# LV1.net
KiCad netlist of a schematic drawn in Altium Designer
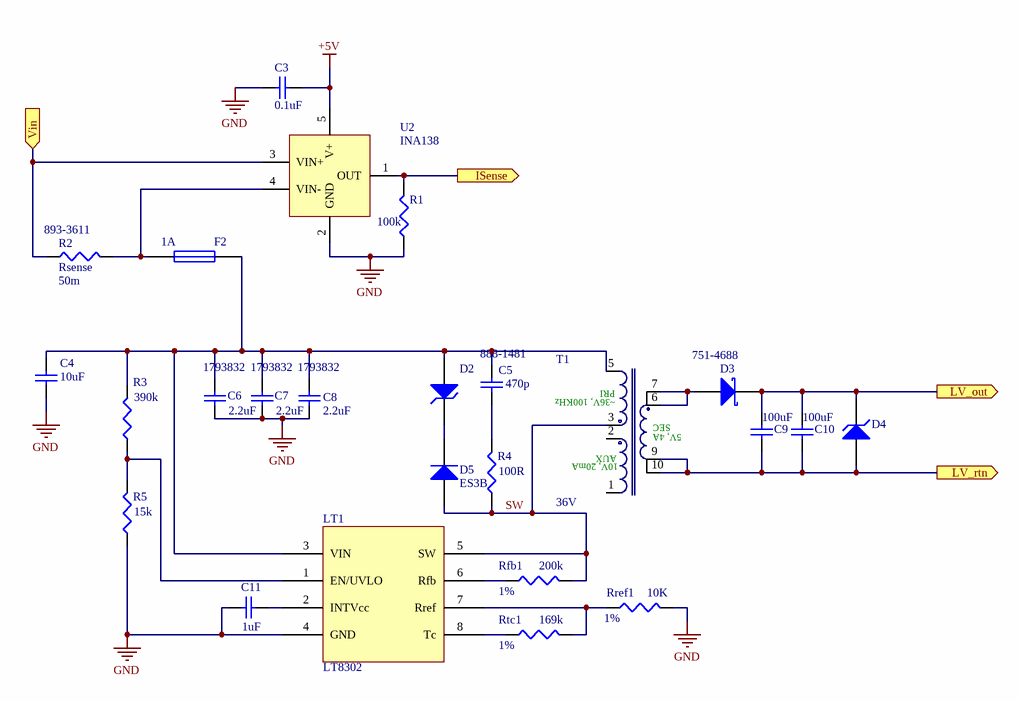
[diagram p0: LV1.schdoc]

(export (version "E")
  (design (tool "Eeschema 10.0.6"))
  (components
    (comp (ref "C3")
      (value "0.1uF")
      (footprint "1608[0603]")
      (description "Capacitor (Semiconductor SIM Model)")
      (fields
        (field (name "PARTNO") "CC0603KRX7R9BB104")
        (field (name "Comment") "Cap Semi")
        (field (name "PUBLISHER") "Altium Limited")
      )
      (libsource (lib "Miscellaneous Devices") (part "Cap Semi"))
    )
    (comp (ref "C4")
      (value "10uF")
      (footprint "C1210")
      (description "Capacitor (Semiconductor SIM Model)")
      (fields
        (field (name "PARTNO") "GRM32ER61H106KA12L")
        (field (name "Comment") "Cap Semi")
        (field (name "PUBLISHER") "Altium Limited")
      )
      (libsource (lib "Miscellaneous Devices") (part "Cap Semi"))
    )
    (comp (ref "C5")
      (value "470p")
      (description "Capacitor (Semiconductor SIM Model)")
      (fields
        (field (name "PARTNO") "08055A221JAT2A")
        (field (name "SUPPLIER PART NUMBER 1") "888-1481")
        (field (name "Comment") "Cap Semi")
        (field (name "PUBLISHER") "Altium Limited")
      )
      (libsource (lib "Miscellaneous Devices") (part "Cap Semi"))
    )
    (comp (ref "C6")
      (value "2.2uF")
      (footprint "C1210")
      (description "Capacitor (Semiconductor SIM Model)")
      (fields
        (field (name "PARTNO") "C1210C225K1RACTU")
        (field (name "SUPPLIER PART NUMBER 1") "1793832")
        (field (name "Comment") "Cap Semi")
        (field (name "PUBLISHER") "Altium Limited")
      )
      (libsource (lib "Miscellaneous Devices") (part "Cap Semi"))
    )
    (comp (ref "C7")
      (value "2.2uF")
      (footprint "C1210")
      (description "Capacitor (Semiconductor SIM Model)")
      (fields
        (field (name "PARTNO") "C1210C225K1RACTU")
        (field (name "SUPPLIER PART NUMBER 1") "1793832")
        (field (name "Comment") "Cap Semi")
        (field (name "PUBLISHER") "Altium Limited")
      )
      (libsource (lib "Miscellaneous Devices") (part "Cap Semi"))
    )
    (comp (ref "C8")
      (value "2.2uF")
      (footprint "C1210")
      (description "Capacitor (Semiconductor SIM Model)")
      (fields
        (field (name "PARTNO") "C1210C225K1RACTU")
        (field (name "SUPPLIER PART NUMBER 1") "1793832")
        (field (name "Comment") "Cap Semi")
        (field (name "PUBLISHER") "Altium Limited")
      )
      (libsource (lib "Miscellaneous Devices") (part "Cap Semi"))
    )
    (comp (ref "C9")
      (value "100uF")
      (footprint "C1210")
      (description "Capacitor (Semiconductor SIM Model)")
      (fields
        (field (name "PARTNO") "C3225X5R0J107M250AC")
        (field (name "Comment") "Cap Semi")
        (field (name "PUBLISHER") "Altium Limited")
      )
      (libsource (lib "Miscellaneous Devices") (part "Cap Semi"))
    )
    (comp (ref "C10")
      (value "100uF")
      (footprint "C1210")
      (description "Capacitor (Semiconductor SIM Model)")
      (fields
        (field (name "PARTNO") "C3225X5R0J107M250AC")
        (field (name "Comment") "Cap Semi")
        (field (name "PUBLISHER") "Altium Limited")
      )
      (libsource (lib "Miscellaneous Devices") (part "Cap Semi"))
    )
    (comp (ref "C11")
      (value "1uF")
      (footprint "1608[0603]")
      (description "Capacitor (Semiconductor SIM Model)")
      (fields
        (field (name "PARTNO") "06033D105KAT2A")
        (field (name "Comment") "Cap Semi")
        (field (name "PUBLISHER") "Altium Limited")
      )
      (libsource (lib "Miscellaneous Devices") (part "Cap Semi"))
    )
    (comp (ref "D2")
      (value "SMAJ30A")
      (footprint "DO-214AC")
      (description "Zener Diode")
      (fields (field (name "PUBLISHER") "Altium Limited"))
      (libsource (lib "Miscellaneous Devices") (part "D Zener"))
    )
    (comp (ref "D3")
      (value "PDS1040L")
      (footprint "PDS1040L")
      (description "Schottky Diode")
      (fields
        (field (name "PARTNO") "SBR15U50SP5-13")
        (field (name "SUPPLIER PART NUMBER 1") "751-4688")
        (field (name "PUBLISHER") "Altium Limited")
      )
      (libsource (lib "G2_LV") (part "PDS1040L"))
    )
    (comp (ref "D4")
      (value "BZT52H-B5V6")
      (footprint "SOD123F")
      (description "Zener Diode")
      (fields (field (name "PUBLISHER") "Altium Limited"))
      (libsource (lib "G2_LV") (part "BZT52H-B5V6"))
    )
    (comp (ref "D5")
      (value "ES3B")
      (footprint "DO-214AB")
      (description "Power Diode")
      (fields (field (name "PUBLISHER") "Altium Limited"))
      (libsource (lib "G2_LV") (part "ES3B"))
    )
    (comp (ref "F2")
      (value "~")
      (footprint "LV1:MC33192")
      (description "Fuse")
      (fields
        (field (name "TRIPPING CURRENT") "1A")
        (field (name "PARTNO") "MC33192")
        (field (name "PUBLISHER") "Altium Limited")
      )
      (libsource (lib "G2_LV") (part "Fuse 1"))
    )
    (comp (ref "LT1")
      (value "LT8302")
      (footprint "S8E")
      (fields (field (name "PARTNO") "LT8302ES8E#PBF"))
      (libsource (lib "G2_LV") (part "LT8302"))
    )
    (comp (ref "R1")
      (value "100k")
      (footprint "J1-0603")
      (description "Resistor")
      (fields (field (name "Comment") "Res3") (field (name "PUBLISHER") "Altium Limited"))
      (libsource (lib "Miscellaneous Devices") (part "Res3"))
    )
    (comp (ref "R2")
      (value "Rsense")
      (footprint "R6432")
      (description "CRF2512-FV-R001ELF")
      (fields
        (field (name "ALTIUM_VALUE") "50m")
        (field (name "PARTNO") "MCS3264R050FER")
        (field (name "SUPPLIER PART NUMBER 1") "893-3611")
        (field (name "PUBLISHER") "Altium Limited")
      )
      (libsource (lib "G2_LV") (part "Rsense"))
    )
    (comp (ref "R3")
      (value "390k")
      (footprint "J1-0603")
      (description "Resistor")
      (fields (field (name "Comment") "Res3") (field (name "PUBLISHER") "Altium Limited"))
      (libsource (lib "Miscellaneous Devices") (part "Res3"))
    )
    (comp (ref "R4")
      (value "100R")
      (description "Resistor")
      (fields
        (field (name "PARTNO") "CRS1206-FX-1000ELF")
        (field (name "Comment") "Res3")
        (field (name "PUBLISHER") "Altium Limited")
      )
      (libsource (lib "Miscellaneous Devices") (part "Res3"))
    )
    (comp (ref "R5")
      (value "15k")
      (footprint "J1-0603")
      (description "Resistor")
      (fields (field (name "Comment") "Res3") (field (name "PUBLISHER") "Altium Limited"))
      (libsource (lib "Miscellaneous Devices") (part "Res3"))
    )
    (comp (ref "Rfb1")
      (value "200k")
      (footprint "J1-0603")
      (description "Resistor")
      (fields
        (field (name "TOLERANCE") "1%")
        (field (name "Comment") "Res3")
        (field (name "PUBLISHER") "Altium Limited")
      )
      (libsource (lib "Miscellaneous Devices") (part "Res3"))
    )
    (comp (ref "Rref1")
      (value "10K")
      (footprint "J1-0603")
      (description "Resistor")
      (fields
        (field (name "TOLERANCE") "1%")
        (field (name "Comment") "Res3")
        (field (name "PUBLISHER") "Altium Limited")
      )
      (libsource (lib "Miscellaneous Devices") (part "Res3"))
    )
    (comp (ref "Rtc1")
      (value "169k")
      (footprint "J1-0603")
      (description "Resistor")
      (fields
        (field (name "TOLERANCE") "1%")
        (field (name "Comment") "Res3")
        (field (name "PUBLISHER") "Altium Limited")
      )
      (libsource (lib "Miscellaneous Devices") (part "Res3"))
    )
    (comp (ref "T1")
      (value "36V")
      (footprint "EP13")
      (description "Flyback Transformer suitable or LT3573/ LT3574/ LT3575/ LT3748 WE-FB, Ui=36V")
      (fields
        (field (name "PARTNO") "750311457")
        (field (name "MANUFACTURER") "Würth Elektronik eiSos GmbH")
        (field (name "CREATED BY") "Otto Christin")
      )
      (libsource (lib "WE-FB") (part "WE-FB, 750311457"))
    )
    (comp (ref "U2")
      (value "INA138")
      (footprint "SOT-23")
      (fields (field (name "PARTNO") "INA138NA/250"))
      (libsource (lib "PCB_Project") (part "INA138"))
    )
  )
  (nets
    (net (code "1") (name "+5V") (class "Default")
      (node (ref "C3") (pin "2") (pinfunction "2_2") (pintype "passive"))
      (node (ref "U2") (pin "5") (pinfunction "V+_5") (pintype "passive"))
    )
    (net (code "2") (name "/ISense") (class "Default")
      (node (ref "R1") (pin "2") (pinfunction "2_2") (pintype "passive"))
      (node (ref "U2") (pin "1") (pinfunction "OUT_1") (pintype "passive"))
    )
    (net (code "3") (name "/LV_out") (class "Default")
      (node (ref "C10") (pin "2") (pinfunction "2_2") (pintype "passive"))
      (node (ref "C9") (pin "2") (pinfunction "2_2") (pintype "passive"))
      (node (ref "D3") (pin "2") (pinfunction "K_2") (pintype "passive"))
      (node (ref "D4") (pin "2") (pinfunction "K_2") (pintype "passive"))
    )
    (net (code "4") (name "/LV_rtn") (class "Default")
      (node (ref "C10") (pin "1") (pinfunction "1_1") (pintype "passive"))
      (node (ref "C9") (pin "1") (pinfunction "1_1") (pintype "passive"))
      (node (ref "D4") (pin "1") (pinfunction "A_1") (pintype "passive"))
      (node (ref "T1") (pin "10") (pinfunction "10_10") (pintype "passive"))
      (node (ref "T1") (pin "9") (pinfunction "9_9") (pintype "passive"))
    )
    (net (code "5") (name "/SW") (class "Default")
      (node (ref "D5") (pin "2") (pinfunction "A_2") (pintype "passive"))
      (node (ref "LT1") (pin "5") (pinfunction "SW_5") (pintype "passive"))
      (node (ref "R4") (pin "1") (pinfunction "1_1") (pintype "passive"))
      (node (ref "Rfb1") (pin "2") (pinfunction "2_2") (pintype "passive"))
      (node (ref "T1") (pin "3") (pinfunction "3_3") (pintype "passive"))
    )
    (net (code "6") (name "/Vin") (class "Default")
      (node (ref "R2") (pin "1") (pinfunction "1_1") (pintype "passive"))
      (node (ref "U2") (pin "3") (pinfunction "VIN+_3") (pintype "passive"))
    )
    (net (code "7") (name "GND") (class "Default")
      (node (ref "C11") (pin "2") (pinfunction "2_2") (pintype "passive"))
      (node (ref "C3") (pin "1") (pinfunction "1_1") (pintype "passive"))
      (node (ref "C4") (pin "1") (pinfunction "1_1") (pintype "passive"))
      (node (ref "C6") (pin "1") (pinfunction "1_1") (pintype "passive"))
      (node (ref "C7") (pin "1") (pinfunction "1_1") (pintype "passive"))
      (node (ref "C8") (pin "1") (pinfunction "1_1") (pintype "passive"))
      (node (ref "LT1") (pin "4") (pinfunction "GND_4") (pintype "passive"))
      (node (ref "R1") (pin "1") (pinfunction "1_1") (pintype "passive"))
      (node (ref "R5") (pin "1") (pinfunction "1_1") (pintype "passive"))
      (node (ref "Rref1") (pin "2") (pinfunction "2_2") (pintype "passive"))
      (node (ref "U2") (pin "2") (pinfunction "GND_2") (pintype "passive"))
    )
    (net (code "8") (name "Net-(C5-Pad1)") (class "Default")
      (node (ref "C5") (pin "1") (pinfunction "1_1") (pintype "passive"))
      (node (ref "R4") (pin "2") (pinfunction "2_2") (pintype "passive"))
    )
    (net (code "9") (name "Net-(D2-A)") (class "Default")
      (node (ref "C4") (pin "2") (pinfunction "2_2") (pintype "passive"))
      (node (ref "C5") (pin "2") (pinfunction "2_2") (pintype "passive"))
      (node (ref "C6") (pin "2") (pinfunction "2_2") (pintype "passive"))
      (node (ref "C7") (pin "2") (pinfunction "2_2") (pintype "passive"))
      (node (ref "C8") (pin "2") (pinfunction "2_2") (pintype "passive"))
      (node (ref "D2") (pin "1") (pinfunction "A_1") (pintype "passive"))
      (node (ref "F2") (pin "2") (pinfunction "2_2") (pintype "passive"))
      (node (ref "LT1") (pin "3") (pinfunction "VIN_3") (pintype "passive"))
      (node (ref "R3") (pin "2") (pinfunction "2_2") (pintype "passive"))
      (node (ref "T1") (pin "5") (pinfunction "5_5") (pintype "passive"))
    )
    (net (code "10") (name "Net-(D2-K)") (class "Default")
      (node (ref "D2") (pin "2") (pinfunction "K_2") (pintype "passive"))
      (node (ref "D5") (pin "1") (pinfunction "K_1") (pintype "passive"))
    )
    (net (code "11") (name "Net-(D3-A)") (class "Default")
      (node (ref "D3") (pin "1") (pinfunction "A_1") (pintype "passive"))
      (node (ref "T1") (pin "6") (pinfunction "6_6") (pintype "passive"))
      (node (ref "T1") (pin "7") (pinfunction "7_7") (pintype "passive"))
    )
    (net (code "12") (name "Net-(LT1-EN{slash}UVLO)") (class "Default")
      (node (ref "LT1") (pin "1") (pinfunction "EN/UVLO_1") (pintype "passive"))
      (node (ref "R3") (pin "1") (pinfunction "1_1") (pintype "passive"))
      (node (ref "R5") (pin "2") (pinfunction "2_2") (pintype "passive"))
    )
    (net (code "13") (name "Net-(LT1-INTVcc)") (class "Default")
      (node (ref "C11") (pin "1") (pinfunction "1_1") (pintype "passive"))
      (node (ref "LT1") (pin "2") (pinfunction "INTVcc_2") (pintype "passive"))
    )
    (net (code "14") (name "Net-(LT1-Rfb)") (class "Default")
      (node (ref "LT1") (pin "6") (pinfunction "Rfb_6") (pintype "passive"))
      (node (ref "Rfb1") (pin "1") (pinfunction "1_1") (pintype "passive"))
    )
    (net (code "15") (name "Net-(LT1-Rref)") (class "Default")
      (node (ref "LT1") (pin "7") (pinfunction "Rref_7") (pintype "passive"))
      (node (ref "Rref1") (pin "1") (pinfunction "1_1") (pintype "passive"))
      (node (ref "Rtc1") (pin "2") (pinfunction "2_2") (pintype "passive"))
    )
    (net (code "16") (name "Net-(LT1-Tc)") (class "Default")
      (node (ref "LT1") (pin "8") (pinfunction "Tc_8") (pintype "passive"))
      (node (ref "Rtc1") (pin "1") (pinfunction "1_1") (pintype "passive"))
    )
    (net (code "17") (name "Net-(U2-VIN-)") (class "Default")
      (node (ref "F2") (pin "1") (pinfunction "1_1") (pintype "passive"))
      (node (ref "R2") (pin "2") (pinfunction "2_2") (pintype "passive"))
      (node (ref "U2") (pin "4") (pinfunction "VIN-_4") (pintype "passive"))
    )
    (net (code "18") (name "unconnected-(T1-Pad1)") (class "Default")
      (node (ref "T1") (pin "1") (pinfunction "1_1") (pintype "passive"))
    )
    (net (code "19") (name "unconnected-(T1-Pad2)") (class "Default")
      (node (ref "T1") (pin "2") (pinfunction "2_2") (pintype "passive"))
    )
  )
)
